# Ring_2_A.net
KiCad netlist of a schematic drawn in Altium Designer
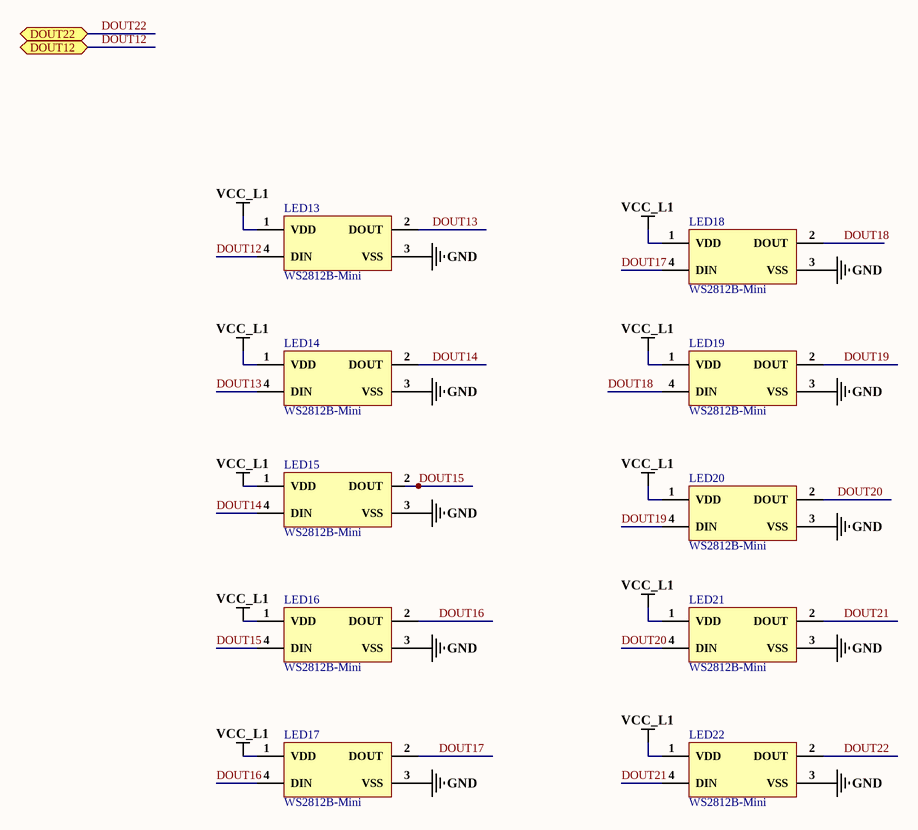
[diagram p0: Ring 2_A.SchDoc]

(export (version "E")
  (design (tool "Eeschema 10.0.6"))
  (components
    (comp (ref "LED13")
      (value "WS2812B-Mini")
      (footprint "WS2812B-Mini")
      (description "SMD,3.5x3.5mm Light Emitting Diodes (LED) RoHS")
      (fields (field (name "MANUFACTURER") "Worldsemi"))
      (libsource (lib "TT_IntLib") (part "WS2812B-Mini"))
    )
    (comp (ref "LED14")
      (value "WS2812B-Mini")
      (footprint "WS2812B-Mini")
      (description "SMD,3.5x3.5mm Light Emitting Diodes (LED) RoHS")
      (fields (field (name "MANUFACTURER") "Worldsemi"))
      (libsource (lib "TT_IntLib") (part "WS2812B-Mini"))
    )
    (comp (ref "LED15")
      (value "WS2812B-Mini")
      (footprint "WS2812B-Mini")
      (description "SMD,3.5x3.5mm Light Emitting Diodes (LED) RoHS")
      (fields (field (name "MANUFACTURER") "Worldsemi"))
      (libsource (lib "TT_IntLib") (part "WS2812B-Mini"))
    )
    (comp (ref "LED16")
      (value "WS2812B-Mini")
      (footprint "WS2812B-Mini")
      (description "SMD,3.5x3.5mm Light Emitting Diodes (LED) RoHS")
      (fields (field (name "MANUFACTURER") "Worldsemi"))
      (libsource (lib "TT_IntLib") (part "WS2812B-Mini"))
    )
    (comp (ref "LED17")
      (value "WS2812B-Mini")
      (footprint "WS2812B-Mini")
      (description "SMD,3.5x3.5mm Light Emitting Diodes (LED) RoHS")
      (fields (field (name "MANUFACTURER") "Worldsemi"))
      (libsource (lib "TT_IntLib") (part "WS2812B-Mini"))
    )
    (comp (ref "LED18")
      (value "WS2812B-Mini")
      (footprint "WS2812B-Mini")
      (description "SMD,3.5x3.5mm Light Emitting Diodes (LED) RoHS")
      (fields (field (name "MANUFACTURER") "Worldsemi"))
      (libsource (lib "TT_IntLib") (part "WS2812B-Mini"))
    )
    (comp (ref "LED19")
      (value "WS2812B-Mini")
      (footprint "WS2812B-Mini")
      (description "SMD,3.5x3.5mm Light Emitting Diodes (LED) RoHS")
      (fields (field (name "MANUFACTURER") "Worldsemi"))
      (libsource (lib "TT_IntLib") (part "WS2812B-Mini"))
    )
    (comp (ref "LED20")
      (value "WS2812B-Mini")
      (footprint "WS2812B-Mini")
      (description "SMD,3.5x3.5mm Light Emitting Diodes (LED) RoHS")
      (fields (field (name "MANUFACTURER") "Worldsemi"))
      (libsource (lib "TT_IntLib") (part "WS2812B-Mini"))
    )
    (comp (ref "LED21")
      (value "WS2812B-Mini")
      (footprint "WS2812B-Mini")
      (description "SMD,3.5x3.5mm Light Emitting Diodes (LED) RoHS")
      (fields (field (name "MANUFACTURER") "Worldsemi"))
      (libsource (lib "TT_IntLib") (part "WS2812B-Mini"))
    )
    (comp (ref "LED22")
      (value "WS2812B-Mini")
      (footprint "WS2812B-Mini")
      (description "SMD,3.5x3.5mm Light Emitting Diodes (LED) RoHS")
      (fields (field (name "MANUFACTURER") "Worldsemi"))
      (libsource (lib "TT_IntLib") (part "WS2812B-Mini"))
    )
  )
  (nets
    (net (code "1") (name "/DOUT12") (class "Default")
      (node (ref "LED13") (pin "4") (pinfunction "DIN_4") (pintype "passive"))
    )
    (net (code "2") (name "/DOUT13") (class "Default")
      (node (ref "LED13") (pin "2") (pinfunction "DOUT_2") (pintype "passive"))
      (node (ref "LED14") (pin "4") (pinfunction "DIN_4") (pintype "passive"))
    )
    (net (code "3") (name "/DOUT14") (class "Default")
      (node (ref "LED14") (pin "2") (pinfunction "DOUT_2") (pintype "passive"))
      (node (ref "LED15") (pin "4") (pinfunction "DIN_4") (pintype "passive"))
    )
    (net (code "4") (name "/DOUT15") (class "Default")
      (node (ref "LED15") (pin "2") (pinfunction "DOUT_2") (pintype "passive"))
      (node (ref "LED16") (pin "4") (pinfunction "DIN_4") (pintype "passive"))
    )
    (net (code "5") (name "/DOUT16") (class "Default")
      (node (ref "LED16") (pin "2") (pinfunction "DOUT_2") (pintype "passive"))
      (node (ref "LED17") (pin "4") (pinfunction "DIN_4") (pintype "passive"))
    )
    (net (code "6") (name "/DOUT17") (class "Default")
      (node (ref "LED17") (pin "2") (pinfunction "DOUT_2") (pintype "passive"))
      (node (ref "LED18") (pin "4") (pinfunction "DIN_4") (pintype "passive"))
    )
    (net (code "7") (name "/DOUT18") (class "Default")
      (node (ref "LED18") (pin "2") (pinfunction "DOUT_2") (pintype "passive"))
      (node (ref "LED19") (pin "4") (pinfunction "DIN_4") (pintype "passive"))
    )
    (net (code "8") (name "/DOUT19") (class "Default")
      (node (ref "LED19") (pin "2") (pinfunction "DOUT_2") (pintype "passive"))
      (node (ref "LED20") (pin "4") (pinfunction "DIN_4") (pintype "passive"))
    )
    (net (code "9") (name "/DOUT20") (class "Default")
      (node (ref "LED20") (pin "2") (pinfunction "DOUT_2") (pintype "passive"))
      (node (ref "LED21") (pin "4") (pinfunction "DIN_4") (pintype "passive"))
    )
    (net (code "10") (name "/DOUT21") (class "Default")
      (node (ref "LED21") (pin "2") (pinfunction "DOUT_2") (pintype "passive"))
      (node (ref "LED22") (pin "4") (pinfunction "DIN_4") (pintype "passive"))
    )
    (net (code "11") (name "/DOUT22") (class "Default")
      (node (ref "LED22") (pin "2") (pinfunction "DOUT_2") (pintype "passive"))
    )
    (net (code "12") (name "GND") (class "Default")
      (node (ref "LED13") (pin "3") (pinfunction "VSS_3") (pintype "passive"))
      (node (ref "LED14") (pin "3") (pinfunction "VSS_3") (pintype "passive"))
      (node (ref "LED15") (pin "3") (pinfunction "VSS_3") (pintype "passive"))
      (node (ref "LED16") (pin "3") (pinfunction "VSS_3") (pintype "passive"))
      (node (ref "LED17") (pin "3") (pinfunction "VSS_3") (pintype "passive"))
      (node (ref "LED18") (pin "3") (pinfunction "VSS_3") (pintype "passive"))
      (node (ref "LED19") (pin "3") (pinfunction "VSS_3") (pintype "passive"))
      (node (ref "LED20") (pin "3") (pinfunction "VSS_3") (pintype "passive"))
      (node (ref "LED21") (pin "3") (pinfunction "VSS_3") (pintype "passive"))
      (node (ref "LED22") (pin "3") (pinfunction "VSS_3") (pintype "passive"))
    )
    (net (code "13") (name "VCC_L1") (class "Default")
      (node (ref "LED13") (pin "1") (pinfunction "VDD_1") (pintype "passive"))
      (node (ref "LED14") (pin "1") (pinfunction "VDD_1") (pintype "passive"))
      (node (ref "LED15") (pin "1") (pinfunction "VDD_1") (pintype "passive"))
      (node (ref "LED16") (pin "1") (pinfunction "VDD_1") (pintype "passive"))
      (node (ref "LED17") (pin "1") (pinfunction "VDD_1") (pintype "passive"))
      (node (ref "LED18") (pin "1") (pinfunction "VDD_1") (pintype "passive"))
      (node (ref "LED19") (pin "1") (pinfunction "VDD_1") (pintype "passive"))
      (node (ref "LED20") (pin "1") (pinfunction "VDD_1") (pintype "passive"))
      (node (ref "LED21") (pin "1") (pinfunction "VDD_1") (pintype "passive"))
      (node (ref "LED22") (pin "1") (pinfunction "VDD_1") (pintype "passive"))
    )
  )
)
